# Entry_Protection.net
KiCad netlist of a schematic drawn in Altium Designer
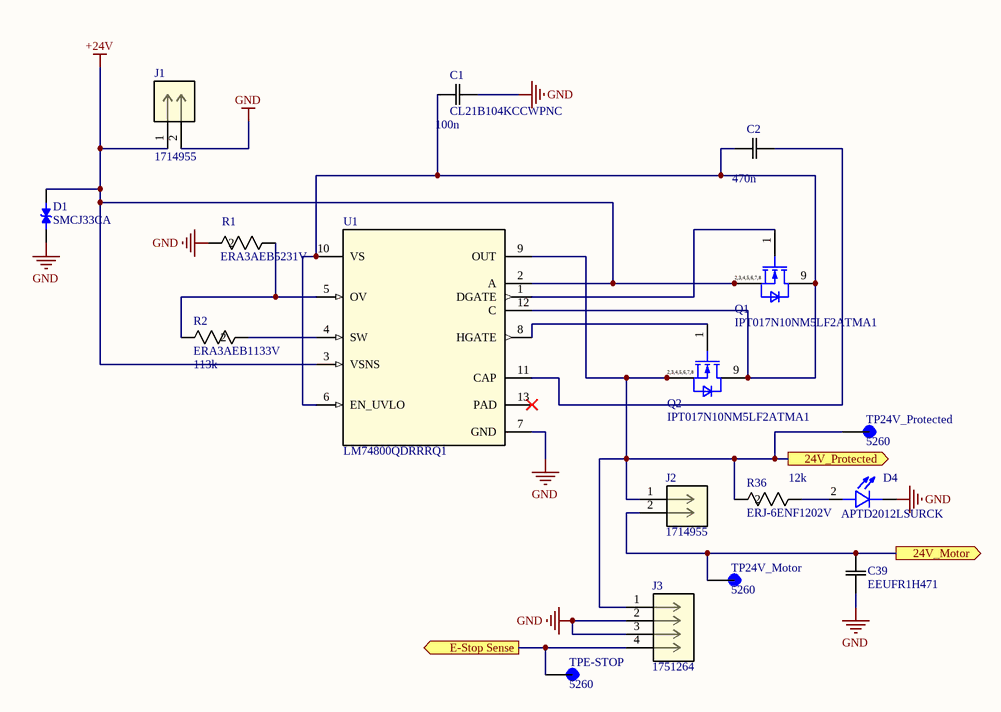
[diagram p0: Entry_Protection.SchDoc]

(export (version "E")
  (design (tool "Eeschema 10.0.6"))
  (components
    (comp (ref "C1")
      (value "CL21B104KCCWPNC")
      (footprint "CAP_CL_21_SAM")
      (description "No Description Available")
      (fields
        (field (name "CAPACITOR") "100n")
        (field (name "COPYRIGHT") "Copyright (C) 2026 Ultra Librarian. All rights reserved.")
      )
      (libsource (lib "Carrier_PBD") (part "CL21B104KCCWPNC"))
    )
    (comp (ref "C2")
      (value "~")
      (footprint "CAP_2012_TDK")
      (description "No Description Available")
      (fields
        (field (name "MANUFACTURER_PART_NUMBER") "C2012X7R1H474K125AB")
        (field (name "CAPACITANCE") "470n")
        (field (name "COPYRIGHT") "Copyright (C) 2026 Ultra Librarian. All rights reserved.")
      )
      (libsource (lib "Carrier_PBD") (part "C2012X7R1H474K125AB"))
    )
    (comp (ref "C39")
      (value "EEUFR1H471")
      (footprint "CAP_12.5 X 20_PAN")
      (description "Description")
      (fields (field (name "COPYRIGHT") "Copyright (C) 2025 Ultra Librarian. All rights reserved."))
      (libsource (lib "Carrier_PBD") (part "EEUFR1H471"))
    )
    (comp (ref "D1")
      (value "SMCJ33CA")
      (footprint "DIOM6859X262N")
      (libsource (lib "Chen-Shi Liou") (part "SMCJ33CA"))
    )
    (comp (ref "D4")
      (value "APTD2012LSURCK")
      (footprint "LED_APTD2012LSURCK")
      (description "Red 630nm LED Indication - Discrete 1.75V 0805 (2012 Metric)")
      (fields (field (name "MF") "Kingbright"))
      (libsource (lib "Chen-Shi Liou") (part "APTD2012LSURCK"))
    )
    (comp (ref "J1")
      (value "1714955")
      (footprint "CONN_1714955_PXC")
      (fields (field (name "COPYRIGHT") "Copyright (C) 2025 Ultra Librarian. All rights reserved."))
      (libsource (lib "") (part "1714955_1"))
    )
    (comp (ref "J2")
      (value "1714955")
      (footprint "CONN_1714955_PXC")
      (fields (field (name "COPYRIGHT") "Copyright (C) 2025 Ultra Librarian. All rights reserved."))
      (libsource (lib "1714955") (part "1714955"))
    )
    (comp (ref "J3")
      (value "1751264")
      (footprint "CONN_1751264_PXC")
      (fields (field (name "COPYRIGHT") "Copyright (C) 2025 Ultra Librarian. All rights reserved."))
      (libsource (lib "1751264") (part "1751264"))
    )
    (comp (ref "Q1")
      (value "IPT017N10NM5LF2ATMA1")
      (footprint "IFX-PG-HSOF-8-1-1-V")
      (fields (field (name "MANUFACTURER") "Infineon Technologies"))
      (libsource (lib "Carrier_PBD") (part "IPT017N10NM5LF2"))
    )
    (comp (ref "Q2")
      (value "IPT017N10NM5LF2ATMA1")
      (footprint "IFX-PG-HSOF-8-1-1-V")
      (fields (field (name "MANUFACTURER") "Infineon Technologies"))
      (libsource (lib "Carrier_PBD") (part "IPT017N10NM5LF2"))
    )
    (comp (ref "R1")
      (value "ERA3AEB5231V")
      (footprint "RES_ERA3A_0603_PAN")
      (description "Description")
      (fields (field (name "COPYRIGHT") "Copyright (C) 2026 Ultra Librarian. All rights reserved."))
      (libsource (lib "Carrier_PBD") (part "ERA3AEB5231V"))
    )
    (comp (ref "R2")
      (value "ERA3AEB1133V")
      (footprint "RES_ERA3A_0603_PAN")
      (description "No Description Available")
      (fields
        (field (name "RESISTANCE") "113k")
        (field (name "COPYRIGHT") "Copyright (C) 2026 Ultra Librarian. All rights reserved.")
      )
      (libsource (lib "ERA3AEB1133V") (part "ERA3AEB1133V"))
    )
    (comp (ref "R36")
      (value "ERJ-6ENF1202V")
      (footprint "RC0805N_PAN")
      (description "Description")
      (fields
        (field (name "RESISTANCE") "12k")
        (field (name "COPYRIGHT") "Copyright (C) 2026 Ultra Librarian. All rights reserved.")
      )
      (libsource (lib "ERJ-6ENF1202V") (part "ERJ-6ENF1202V"))
    )
    (comp (ref "TP24V_Motor")
      (value "5260")
      (footprint "KEYSTONE_5260")
      (description "TEST POINT (RED) - MINIATURE")
      (fields (field (name "MF") "Keystone Electronics"))
      (libsource (lib "Chen-Shi Liou") (part "5260"))
    )
    (comp (ref "TP24V_Protected")
      (value "5260")
      (footprint "KEYSTONE_5260")
      (description "TEST POINT (RED) - MINIATURE")
      (fields (field (name "MF") "Keystone Electronics"))
      (libsource (lib "Chen-Shi Liou") (part "5260"))
    )
    (comp (ref "TPE-STOP")
      (value "5260")
      (footprint "KEYSTONE_5260")
      (description "TEST POINT (RED) - MINIATURE")
      (fields (field (name "MF") "Keystone Electronics"))
      (libsource (lib "Chen-Shi Liou") (part "5260"))
    )
    (comp (ref "U1")
      (value "LM74800QDRRRQ1")
      (footprint "DRR0012E")
      (description "3-V to 65-V, automotive ideal diode controller driving back to back NFETs 12-WSON -40 to 125")
      (fields (field (name "COPYRIGHT") "Copyright (C) 2026 Ultra Librarian. All rights reserved."))
      (libsource (lib "LM74800QDRRRQ1") (part "LM74800QDRRRQ1"))
    )
  )
  (nets
    (net (code "1") (name "+24V") (class "Default")
      (node (ref "D1") (pin "2") (pinfunction "2_2") (pintype "passive"))
      (node (ref "J1") (pin "1") (pinfunction "1_1") (pintype "passive"))
      (node (ref "Q1") (pin "2") (pinfunction "SOURCE_2") (pintype "passive"))
      (node (ref "Q1") (pin "3") (pinfunction "SOURCE_3") (pintype "passive"))
      (node (ref "Q1") (pin "4") (pinfunction "SOURCE_4") (pintype "passive"))
      (node (ref "Q1") (pin "5") (pinfunction "SOURCE_5") (pintype "passive"))
      (node (ref "Q1") (pin "6") (pinfunction "SOURCE_6") (pintype "passive"))
      (node (ref "Q1") (pin "7") (pinfunction "SOURCE_7") (pintype "passive"))
      (node (ref "Q1") (pin "8") (pinfunction "SOURCE_8") (pintype "passive"))
      (node (ref "U1") (pin "2") (pinfunction "A_2") (pintype "passive"))
      (node (ref "U1") (pin "3") (pinfunction "VSNS_3") (pintype "input"))
    )
    (net (code "2") (name "/24V_Motor") (class "Default")
      (node (ref "C39") (pin "1") (pinfunction "1_1") (pintype "passive"))
      (node (ref "J2") (pin "2") (pinfunction "2_2") (pintype "passive"))
      (node (ref "TP24V_Motor") (pin "1") (pinfunction "TP_1") (pintype "passive"))
    )
    (net (code "3") (name "/24V_Protected") (class "Default")
      (node (ref "J2") (pin "1") (pinfunction "1_1") (pintype "passive"))
      (node (ref "J3") (pin "1") (pinfunction "1_1") (pintype "passive"))
      (node (ref "Q2") (pin "2") (pinfunction "SOURCE_2") (pintype "passive"))
      (node (ref "Q2") (pin "3") (pinfunction "SOURCE_3") (pintype "passive"))
      (node (ref "Q2") (pin "4") (pinfunction "SOURCE_4") (pintype "passive"))
      (node (ref "Q2") (pin "5") (pinfunction "SOURCE_5") (pintype "passive"))
      (node (ref "Q2") (pin "6") (pinfunction "SOURCE_6") (pintype "passive"))
      (node (ref "Q2") (pin "7") (pinfunction "SOURCE_7") (pintype "passive"))
      (node (ref "Q2") (pin "8") (pinfunction "SOURCE_8") (pintype "passive"))
      (node (ref "R36") (pin "2") (pinfunction "2_2") (pintype "passive"))
      (node (ref "TP24V_Protected") (pin "1") (pinfunction "TP_1") (pintype "passive"))
      (node (ref "U1") (pin "9") (pinfunction "OUT_9") (pintype "passive"))
    )
    (net (code "4") (name "/E-Stop Sense") (class "Default")
      (node (ref "J3") (pin "4") (pinfunction "4_4") (pintype "passive"))
      (node (ref "TPE-STOP") (pin "1") (pinfunction "TP_1") (pintype "passive"))
    )
    (net (code "5") (name "GND") (class "Default")
      (node (ref "C1") (pin "2") (pinfunction "2_2") (pintype "passive"))
      (node (ref "C39") (pin "2") (pinfunction "2_2") (pintype "passive"))
      (node (ref "D1") (pin "1") (pinfunction "1_1") (pintype "passive"))
      (node (ref "D4") (pin "1") (pinfunction "C_1") (pintype "passive"))
      (node (ref "J1") (pin "2") (pinfunction "2_2") (pintype "passive"))
      (node (ref "J3") (pin "2") (pinfunction "2_2") (pintype "passive"))
      (node (ref "J3") (pin "3") (pinfunction "3_3") (pintype "passive"))
      (node (ref "R1") (pin "2") (pinfunction "2_2") (pintype "passive"))
      (node (ref "U1") (pin "7") (pinfunction "GND_7") (pintype "power_in"))
    )
    (net (code "6") (name "Net-(D4-A)") (class "Default")
      (node (ref "D4") (pin "2") (pinfunction "A_2") (pintype "passive"))
      (node (ref "R36") (pin "1") (pinfunction "1_1") (pintype "passive"))
    )
    (net (code "7") (name "Net-(Q1-DRAIN)") (class "Default")
      (node (ref "C1") (pin "1") (pinfunction "1_1") (pintype "passive"))
      (node (ref "C2") (pin "1") (pinfunction "1_1") (pintype "passive"))
      (node (ref "Q1") (pin "9") (pinfunction "DRAIN_9") (pintype "passive"))
      (node (ref "Q2") (pin "9") (pinfunction "DRAIN_9") (pintype "passive"))
      (node (ref "U1") (pin "10") (pinfunction "VS_10") (pintype "power_in"))
      (node (ref "U1") (pin "12") (pinfunction "C_12") (pintype "passive"))
      (node (ref "U1") (pin "6") (pinfunction "EN_UVLO_6") (pintype "input"))
    )
    (net (code "8") (name "Net-(Q1-GATE)") (class "Default")
      (node (ref "Q1") (pin "1") (pinfunction "GATE_1") (pintype "passive"))
      (node (ref "U1") (pin "1") (pinfunction "DGATE_1") (pintype "output"))
    )
    (net (code "9") (name "Net-(Q2-GATE)") (class "Default")
      (node (ref "Q2") (pin "1") (pinfunction "GATE_1") (pintype "passive"))
      (node (ref "U1") (pin "8") (pinfunction "HGATE_8") (pintype "output"))
    )
    (net (code "10") (name "Net-(U1-CAP)") (class "Default")
      (node (ref "C2") (pin "2") (pinfunction "2_2") (pintype "passive"))
      (node (ref "U1") (pin "11") (pinfunction "CAP_11") (pintype "passive"))
    )
    (net (code "11") (name "Net-(U1-OV)") (class "Default")
      (node (ref "R1") (pin "1") (pinfunction "1_1") (pintype "passive"))
      (node (ref "R2") (pin "1") (pinfunction "1_1") (pintype "passive"))
      (node (ref "U1") (pin "5") (pinfunction "OV_5") (pintype "input"))
    )
    (net (code "12") (name "Net-(U1-SW)") (class "Default")
      (node (ref "R2") (pin "2") (pinfunction "2_2") (pintype "passive"))
      (node (ref "U1") (pin "4") (pinfunction "SW_4") (pintype "input"))
    )
    (net (code "13") (name "unconnected-(U1-PAD-Pad13)") (class "Default")
      (node (ref "U1") (pin "13") (pinfunction "PAD_13") (pintype "passive+no_connect"))
    )
  )
)
